# vme_can_fpga_pwr.net
KiCad netlist of a schematic drawn in Altium Designer
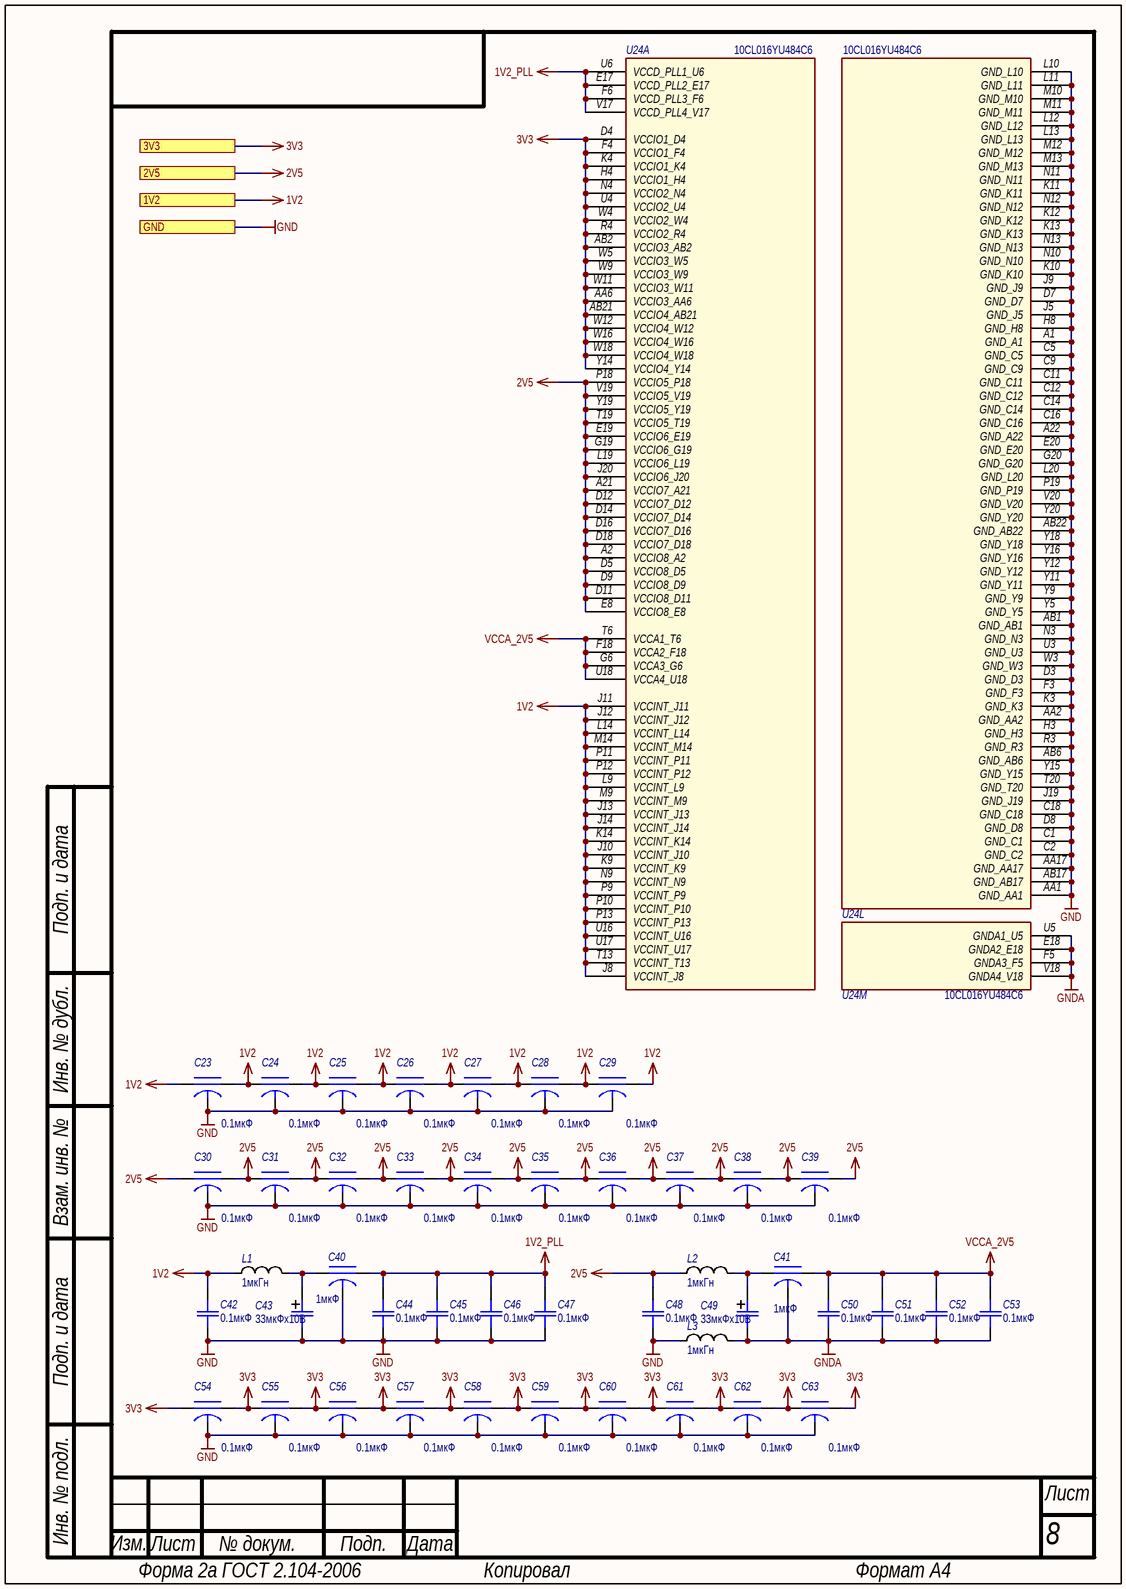
[diagram p0: vme_can_fpga_pwr.SchDoc]

(export (version "E")
  (design (tool "Eeschema 10.0.6"))
  (components
    (comp (ref "C23")
      (value "0.1мкФ")
      (footprint "3pol_SMD0402")
      (fields (field (name "Comment") "NFM15PC104D0J3"))
      (libsource (lib "Capacitop_3Pol") (part "Capacitop_3Pol"))
    )
    (comp (ref "C24")
      (value "0.1мкФ")
      (footprint "3pol_SMD0402")
      (fields (field (name "Comment") "NFM15PC104D0J3"))
      (libsource (lib "Capacitop_3Pol") (part "Capacitop_3Pol"))
    )
    (comp (ref "C25")
      (value "0.1мкФ")
      (footprint "3pol_SMD0402")
      (fields (field (name "Comment") "NFM15PC104D0J3"))
      (libsource (lib "Capacitop_3Pol") (part "Capacitop_3Pol"))
    )
    (comp (ref "C26")
      (value "0.1мкФ")
      (footprint "3pol_SMD0402")
      (fields (field (name "Comment") "NFM15PC104D0J3"))
      (libsource (lib "Capacitop_3Pol") (part "Capacitop_3Pol"))
    )
    (comp (ref "C27")
      (value "0.1мкФ")
      (footprint "3pol_SMD0402")
      (fields (field (name "Comment") "NFM15PC104D0J3"))
      (libsource (lib "Capacitop_3Pol") (part "Capacitop_3Pol"))
    )
    (comp (ref "C28")
      (value "0.1мкФ")
      (footprint "3pol_SMD0402")
      (fields (field (name "Comment") "NFM15PC104D0J3"))
      (libsource (lib "Capacitop_3Pol") (part "Capacitop_3Pol"))
    )
    (comp (ref "C29")
      (value "0.1мкФ")
      (footprint "3pol_SMD0402")
      (fields (field (name "Comment") "NFM15PC104D0J3"))
      (libsource (lib "Capacitop_3Pol") (part "Capacitop_3Pol"))
    )
    (comp (ref "C30")
      (value "0.1мкФ")
      (footprint "3pol_SMD0402")
      (fields (field (name "Comment") "NFM15PC104D0J3"))
      (libsource (lib "Capacitop_3Pol") (part "Capacitop_3Pol"))
    )
    (comp (ref "C31")
      (value "0.1мкФ")
      (footprint "3pol_SMD0402")
      (fields (field (name "Comment") "NFM15PC104D0J3"))
      (libsource (lib "Capacitop_3Pol") (part "Capacitop_3Pol"))
    )
    (comp (ref "C32")
      (value "0.1мкФ")
      (footprint "3pol_SMD0402")
      (fields (field (name "Comment") "NFM15PC104D0J3"))
      (libsource (lib "Capacitop_3Pol") (part "Capacitop_3Pol"))
    )
    (comp (ref "C33")
      (value "0.1мкФ")
      (footprint "3pol_SMD0402")
      (fields (field (name "Comment") "NFM15PC104D0J3"))
      (libsource (lib "Capacitop_3Pol") (part "Capacitop_3Pol"))
    )
    (comp (ref "C34")
      (value "0.1мкФ")
      (footprint "3pol_SMD0402")
      (fields (field (name "Comment") "NFM15PC104D0J3"))
      (libsource (lib "Capacitop_3Pol") (part "Capacitop_3Pol"))
    )
    (comp (ref "C35")
      (value "0.1мкФ")
      (footprint "3pol_SMD0402")
      (fields (field (name "Comment") "NFM15PC104D0J3"))
      (libsource (lib "Capacitop_3Pol") (part "Capacitop_3Pol"))
    )
    (comp (ref "C36")
      (value "0.1мкФ")
      (footprint "3pol_SMD0402")
      (fields (field (name "Comment") "NFM15PC104D0J3"))
      (libsource (lib "Capacitop_3Pol") (part "Capacitop_3Pol"))
    )
    (comp (ref "C37")
      (value "0.1мкФ")
      (footprint "3pol_SMD0402")
      (fields (field (name "Comment") "NFM15PC104D0J3"))
      (libsource (lib "Capacitop_3Pol") (part "Capacitop_3Pol"))
    )
    (comp (ref "C38")
      (value "0.1мкФ")
      (footprint "3pol_SMD0402")
      (fields (field (name "Comment") "NFM15PC104D0J3"))
      (libsource (lib "Capacitop_3Pol") (part "Capacitop_3Pol"))
    )
    (comp (ref "C39")
      (value "0.1мкФ")
      (footprint "3pol_SMD0402")
      (fields (field (name "Comment") "NFM15PC104D0J3"))
      (libsource (lib "Capacitop_3Pol") (part "Capacitop_3Pol"))
    )
    (comp (ref "C40")
      (value "1мкФ")
      (footprint "3pol_SMD0402")
      (fields (field (name "Comment") "NFM15PC105D0J3"))
      (libsource (lib "Capacitop_3Pol") (part "Capacitop_3Pol"))
    )
    (comp (ref "C41")
      (value "1мкФ")
      (footprint "3pol_SMD0402")
      (fields (field (name "Comment") "NFM15PC105D0J3"))
      (libsource (lib "Capacitop_3Pol") (part "Capacitop_3Pol"))
    )
    (comp (ref "C42")
      (value "0.1мкФ")
      (footprint "SMD_C0402")
      (description "Capacitor")
      (libsource (lib "Passive") (part "Capacitor"))
    )
    (comp (ref "C43")
      (value "33мкФх10В")
      (footprint "SMD_size_B")
      (description "Polarized capacitor")
      (libsource (lib "Passive") (part "Capacitor_pol"))
    )
    (comp (ref "C44")
      (value "0.1мкФ")
      (footprint "SMD_C0402")
      (description "Capacitor")
      (libsource (lib "Passive") (part "Capacitor"))
    )
    (comp (ref "C45")
      (value "0.1мкФ")
      (footprint "SMD_C0402")
      (description "Capacitor")
      (libsource (lib "Passive") (part "Capacitor"))
    )
    (comp (ref "C46")
      (value "0.1мкФ")
      (footprint "SMD_C0402")
      (description "Capacitor")
      (libsource (lib "Passive") (part "Capacitor"))
    )
    (comp (ref "C47")
      (value "0.1мкФ")
      (footprint "SMD_C0402")
      (description "Capacitor")
      (libsource (lib "Passive") (part "Capacitor"))
    )
    (comp (ref "C48")
      (value "0.1мкФ")
      (footprint "SMD_C0402")
      (description "Capacitor")
      (libsource (lib "Passive") (part "Capacitor"))
    )
    (comp (ref "C49")
      (value "33мкФх10В")
      (footprint "SMD_size_B")
      (description "Polarized capacitor")
      (libsource (lib "Passive") (part "Capacitor_pol"))
    )
    (comp (ref "C50")
      (value "0.1мкФ")
      (footprint "SMD_C0402")
      (description "Capacitor")
      (libsource (lib "Passive") (part "Capacitor"))
    )
    (comp (ref "C51")
      (value "0.1мкФ")
      (footprint "SMD_C0402")
      (description "Capacitor")
      (libsource (lib "Passive") (part "Capacitor"))
    )
    (comp (ref "C52")
      (value "0.1мкФ")
      (footprint "SMD_C0402")
      (description "Capacitor")
      (libsource (lib "Passive") (part "Capacitor"))
    )
    (comp (ref "C53")
      (value "0.1мкФ")
      (footprint "SMD_C0402")
      (description "Capacitor")
      (libsource (lib "Passive") (part "Capacitor"))
    )
    (comp (ref "C54")
      (value "0.1мкФ")
      (footprint "3pol_SMD0402")
      (fields (field (name "Comment") "NFM15PC104D0J3"))
      (libsource (lib "Capacitop_3Pol") (part "Capacitop_3Pol"))
    )
    (comp (ref "C55")
      (value "0.1мкФ")
      (footprint "3pol_SMD0402")
      (fields (field (name "Comment") "NFM15PC104D0J3"))
      (libsource (lib "Capacitop_3Pol") (part "Capacitop_3Pol"))
    )
    (comp (ref "C56")
      (value "0.1мкФ")
      (footprint "3pol_SMD0402")
      (fields (field (name "Comment") "NFM15PC104D0J3"))
      (libsource (lib "Capacitop_3Pol") (part "Capacitop_3Pol"))
    )
    (comp (ref "C57")
      (value "0.1мкФ")
      (footprint "3pol_SMD0402")
      (fields (field (name "Comment") "NFM15PC104D0J3"))
      (libsource (lib "Capacitop_3Pol") (part "Capacitop_3Pol"))
    )
    (comp (ref "C58")
      (value "0.1мкФ")
      (footprint "3pol_SMD0402")
      (fields (field (name "Comment") "NFM15PC104D0J3"))
      (libsource (lib "Capacitop_3Pol") (part "Capacitop_3Pol"))
    )
    (comp (ref "C59")
      (value "0.1мкФ")
      (footprint "3pol_SMD0402")
      (fields (field (name "Comment") "NFM15PC104D0J3"))
      (libsource (lib "Capacitop_3Pol") (part "Capacitop_3Pol"))
    )
    (comp (ref "C60")
      (value "0.1мкФ")
      (footprint "3pol_SMD0402")
      (fields (field (name "Comment") "NFM15PC104D0J3"))
      (libsource (lib "Capacitop_3Pol") (part "Capacitop_3Pol"))
    )
    (comp (ref "C61")
      (value "0.1мкФ")
      (footprint "3pol_SMD0402")
      (fields (field (name "Comment") "NFM15PC104D0J3"))
      (libsource (lib "Capacitop_3Pol") (part "Capacitop_3Pol"))
    )
    (comp (ref "C62")
      (value "0.1мкФ")
      (footprint "3pol_SMD0402")
      (fields (field (name "Comment") "NFM15PC104D0J3"))
      (libsource (lib "Capacitop_3Pol") (part "Capacitop_3Pol"))
    )
    (comp (ref "C63")
      (value "0.1мкФ")
      (footprint "3pol_SMD0402")
      (fields (field (name "Comment") "NFM15PC104D0J3"))
      (libsource (lib "Capacitop_3Pol") (part "Capacitop_3Pol"))
    )
    (comp (ref "L1")
      (value "1мкГн")
      (footprint "SMD_0805")
      (description "Inductor")
      (libsource (lib "Passive") (part "Inductor"))
    )
    (comp (ref "L2")
      (value "1мкГн")
      (footprint "SMD_0805")
      (description "Inductor")
      (libsource (lib "Passive") (part "Inductor"))
    )
    (comp (ref "L3")
      (value "1мкГн")
      (footprint "SMD_0805")
      (description "Inductor")
      (libsource (lib "Passive") (part "Inductor"))
    )
    (comp (ref "U24")
      (value "10CL016YU484")
      (footprint "UBGA-484")
      (description "Intel® Cyclone® 10 LP FPGA")
      (fields (field (name "НАИМЕНОВАНИЕ") "10CL016YU484С6"))
      (libsource (lib "FPGA") (part "10CL016_U484"))
    )
  )
  (nets
    (net (code "1") (name "1V2") (class "Default")
      (node (ref "C23") (pin "1") (pinfunction "Input_1") (pintype "passive"))
      (node (ref "C23") (pin "3") (pinfunction "Output_3") (pintype "passive"))
      (node (ref "C24") (pin "1") (pinfunction "Input_1") (pintype "passive"))
      (node (ref "C24") (pin "3") (pinfunction "Output_3") (pintype "passive"))
      (node (ref "C25") (pin "1") (pinfunction "Input_1") (pintype "passive"))
      (node (ref "C25") (pin "3") (pinfunction "Output_3") (pintype "passive"))
      (node (ref "C26") (pin "1") (pinfunction "Input_1") (pintype "passive"))
      (node (ref "C26") (pin "3") (pinfunction "Output_3") (pintype "passive"))
      (node (ref "C27") (pin "1") (pinfunction "Input_1") (pintype "passive"))
      (node (ref "C27") (pin "3") (pinfunction "Output_3") (pintype "passive"))
      (node (ref "C28") (pin "1") (pinfunction "Input_1") (pintype "passive"))
      (node (ref "C28") (pin "3") (pinfunction "Output_3") (pintype "passive"))
      (node (ref "C29") (pin "1") (pinfunction "Input_1") (pintype "passive"))
      (node (ref "C29") (pin "3") (pinfunction "Output_3") (pintype "passive"))
      (node (ref "C42") (pin "2") (pinfunction "2_2") (pintype "passive"))
      (node (ref "L1") (pin "2") (pinfunction "2_2") (pintype "passive"))
      (node (ref "U24") (pin "J10") (pinfunction "VCCINT_J10_J10") (pintype "power_in"))
      (node (ref "U24") (pin "J11") (pinfunction "VCCINT_J11_J11") (pintype "power_in"))
      (node (ref "U24") (pin "J12") (pinfunction "VCCINT_J12_J12") (pintype "power_in"))
      (node (ref "U24") (pin "J13") (pinfunction "VCCINT_J13_J13") (pintype "power_in"))
      (node (ref "U24") (pin "J14") (pinfunction "VCCINT_J14_J14") (pintype "power_in"))
      (node (ref "U24") (pin "J8") (pinfunction "VCCINT_J8_J8") (pintype "power_in"))
      (node (ref "U24") (pin "K14") (pinfunction "VCCINT_K14_K14") (pintype "power_in"))
      (node (ref "U24") (pin "K9") (pinfunction "VCCINT_K9_K9") (pintype "power_in"))
      (node (ref "U24") (pin "L14") (pinfunction "VCCINT_L14_L14") (pintype "power_in"))
      (node (ref "U24") (pin "L9") (pinfunction "VCCINT_L9_L9") (pintype "power_in"))
      (node (ref "U24") (pin "M14") (pinfunction "VCCINT_M14_M14") (pintype "power_in"))
      (node (ref "U24") (pin "M9") (pinfunction "VCCINT_M9_M9") (pintype "power_in"))
      (node (ref "U24") (pin "N9") (pinfunction "VCCINT_N9_N9") (pintype "power_in"))
      (node (ref "U24") (pin "P10") (pinfunction "VCCINT_P10_P10") (pintype "power_in"))
      (node (ref "U24") (pin "P11") (pinfunction "VCCINT_P11_P11") (pintype "power_in"))
      (node (ref "U24") (pin "P12") (pinfunction "VCCINT_P12_P12") (pintype "power_in"))
      (node (ref "U24") (pin "P13") (pinfunction "VCCINT_P13_P13") (pintype "power_in"))
      (node (ref "U24") (pin "P9") (pinfunction "VCCINT_P9_P9") (pintype "power_in"))
      (node (ref "U24") (pin "T13") (pinfunction "VCCINT_T13_T13") (pintype "power_in"))
      (node (ref "U24") (pin "U16") (pinfunction "VCCINT_U16_U16") (pintype "power_in"))
      (node (ref "U24") (pin "U17") (pinfunction "VCCINT_U17_U17") (pintype "power_in"))
    )
    (net (code "2") (name "1V2_PLL") (class "Default")
      (node (ref "C40") (pin "1") (pinfunction "Input_1") (pintype "passive"))
      (node (ref "C44") (pin "2") (pinfunction "2_2") (pintype "passive"))
      (node (ref "C45") (pin "2") (pinfunction "2_2") (pintype "passive"))
      (node (ref "C46") (pin "2") (pinfunction "2_2") (pintype "passive"))
      (node (ref "C47") (pin "2") (pinfunction "2_2") (pintype "passive"))
      (node (ref "U24") (pin "E17") (pinfunction "VCCD_PLL2_E17_E17") (pintype "power_in"))
      (node (ref "U24") (pin "F6") (pinfunction "VCCD_PLL3_F6_F6") (pintype "power_in"))
      (node (ref "U24") (pin "U6") (pinfunction "VCCD_PLL1_U6_U6") (pintype "power_in"))
      (node (ref "U24") (pin "V17") (pinfunction "VCCD_PLL4_V17_V17") (pintype "power_in"))
    )
    (net (code "3") (name "2V5") (class "Default")
      (node (ref "C30") (pin "1") (pinfunction "Input_1") (pintype "passive"))
      (node (ref "C30") (pin "3") (pinfunction "Output_3") (pintype "passive"))
      (node (ref "C31") (pin "1") (pinfunction "Input_1") (pintype "passive"))
      (node (ref "C31") (pin "3") (pinfunction "Output_3") (pintype "passive"))
      (node (ref "C32") (pin "1") (pinfunction "Input_1") (pintype "passive"))
      (node (ref "C32") (pin "3") (pinfunction "Output_3") (pintype "passive"))
      (node (ref "C33") (pin "1") (pinfunction "Input_1") (pintype "passive"))
      (node (ref "C33") (pin "3") (pinfunction "Output_3") (pintype "passive"))
      (node (ref "C34") (pin "1") (pinfunction "Input_1") (pintype "passive"))
      (node (ref "C34") (pin "3") (pinfunction "Output_3") (pintype "passive"))
      (node (ref "C35") (pin "1") (pinfunction "Input_1") (pintype "passive"))
      (node (ref "C35") (pin "3") (pinfunction "Output_3") (pintype "passive"))
      (node (ref "C36") (pin "1") (pinfunction "Input_1") (pintype "passive"))
      (node (ref "C36") (pin "3") (pinfunction "Output_3") (pintype "passive"))
      (node (ref "C37") (pin "1") (pinfunction "Input_1") (pintype "passive"))
      (node (ref "C37") (pin "3") (pinfunction "Output_3") (pintype "passive"))
      (node (ref "C38") (pin "1") (pinfunction "Input_1") (pintype "passive"))
      (node (ref "C38") (pin "3") (pinfunction "Output_3") (pintype "passive"))
      (node (ref "C39") (pin "1") (pinfunction "Input_1") (pintype "passive"))
      (node (ref "C39") (pin "3") (pinfunction "Output_3") (pintype "passive"))
      (node (ref "C48") (pin "2") (pinfunction "2_2") (pintype "passive"))
      (node (ref "L2") (pin "2") (pinfunction "2_2") (pintype "passive"))
      (node (ref "U24") (pin "A2") (pinfunction "VCCIO8_A2_A2") (pintype "power_in"))
      (node (ref "U24") (pin "A21") (pinfunction "VCCIO7_A21_A21") (pintype "power_in"))
      (node (ref "U24") (pin "D11") (pinfunction "VCCIO8_D11_D11") (pintype "power_in"))
      (node (ref "U24") (pin "D12") (pinfunction "VCCIO7_D12_D12") (pintype "power_in"))
      (node (ref "U24") (pin "D14") (pinfunction "VCCIO7_D14_D14") (pintype "power_in"))
      (node (ref "U24") (pin "D16") (pinfunction "VCCIO7_D16_D16") (pintype "power_in"))
      (node (ref "U24") (pin "D18") (pinfunction "VCCIO7_D18_D18") (pintype "power_in"))
      (node (ref "U24") (pin "D5") (pinfunction "VCCIO8_D5_D5") (pintype "power_in"))
      (node (ref "U24") (pin "D9") (pinfunction "VCCIO8_D9_D9") (pintype "power_in"))
      (node (ref "U24") (pin "E19") (pinfunction "VCCIO6_E19_E19") (pintype "power_in"))
      (node (ref "U24") (pin "E8") (pinfunction "VCCIO8_E8_E8") (pintype "power_in"))
      (node (ref "U24") (pin "G19") (pinfunction "VCCIO6_G19_G19") (pintype "power_in"))
      (node (ref "U24") (pin "J20") (pinfunction "VCCIO6_J20_J20") (pintype "power_in"))
      (node (ref "U24") (pin "L19") (pinfunction "VCCIO6_L19_L19") (pintype "power_in"))
      (node (ref "U24") (pin "P18") (pinfunction "VCCIO5_P18_P18") (pintype "power_in"))
      (node (ref "U24") (pin "T19") (pinfunction "VCCIO5_T19_T19") (pintype "power_in"))
      (node (ref "U24") (pin "V19") (pinfunction "VCCIO5_V19_V19") (pintype "power_in"))
      (node (ref "U24") (pin "Y19") (pinfunction "VCCIO5_Y19_Y19") (pintype "power_in"))
    )
    (net (code "4") (name "3V3") (class "Default")
      (node (ref "C54") (pin "1") (pinfunction "Input_1") (pintype "passive"))
      (node (ref "C54") (pin "3") (pinfunction "Output_3") (pintype "passive"))
      (node (ref "C55") (pin "1") (pinfunction "Input_1") (pintype "passive"))
      (node (ref "C55") (pin "3") (pinfunction "Output_3") (pintype "passive"))
      (node (ref "C56") (pin "1") (pinfunction "Input_1") (pintype "passive"))
      (node (ref "C56") (pin "3") (pinfunction "Output_3") (pintype "passive"))
      (node (ref "C57") (pin "1") (pinfunction "Input_1") (pintype "passive"))
      (node (ref "C57") (pin "3") (pinfunction "Output_3") (pintype "passive"))
      (node (ref "C58") (pin "1") (pinfunction "Input_1") (pintype "passive"))
      (node (ref "C58") (pin "3") (pinfunction "Output_3") (pintype "passive"))
      (node (ref "C59") (pin "1") (pinfunction "Input_1") (pintype "passive"))
      (node (ref "C59") (pin "3") (pinfunction "Output_3") (pintype "passive"))
      (node (ref "C60") (pin "1") (pinfunction "Input_1") (pintype "passive"))
      (node (ref "C60") (pin "3") (pinfunction "Output_3") (pintype "passive"))
      (node (ref "C61") (pin "1") (pinfunction "Input_1") (pintype "passive"))
      (node (ref "C61") (pin "3") (pinfunction "Output_3") (pintype "passive"))
      (node (ref "C62") (pin "1") (pinfunction "Input_1") (pintype "passive"))
      (node (ref "C62") (pin "3") (pinfunction "Output_3") (pintype "passive"))
      (node (ref "C63") (pin "1") (pinfunction "Input_1") (pintype "passive"))
      (node (ref "C63") (pin "3") (pinfunction "Output_3") (pintype "passive"))
      (node (ref "U24") (pin "AA6") (pinfunction "VCCIO3_AA6_AA6") (pintype "power_in"))
      (node (ref "U24") (pin "AB2") (pinfunction "VCCIO3_AB2_AB2") (pintype "power_in"))
      (node (ref "U24") (pin "AB21") (pinfunction "VCCIO4_AB21_AB21") (pintype "power_in"))
      (node (ref "U24") (pin "D4") (pinfunction "VCCIO1_D4_D4") (pintype "power_in"))
      (node (ref "U24") (pin "F4") (pinfunction "VCCIO1_F4_F4") (pintype "power_in"))
      (node (ref "U24") (pin "H4") (pinfunction "VCCIO1_H4_H4") (pintype "power_in"))
      (node (ref "U24") (pin "K4") (pinfunction "VCCIO1_K4_K4") (pintype "power_in"))
      (node (ref "U24") (pin "N4") (pinfunction "VCCIO2_N4_N4") (pintype "power_in"))
      (node (ref "U24") (pin "R4") (pinfunction "VCCIO2_R4_R4") (pintype "power_in"))
      (node (ref "U24") (pin "U4") (pinfunction "VCCIO2_U4_U4") (pintype "power_in"))
      (node (ref "U24") (pin "W11") (pinfunction "VCCIO3_W11_W11") (pintype "power_in"))
      (node (ref "U24") (pin "W12") (pinfunction "VCCIO4_W12_W12") (pintype "power_in"))
      (node (ref "U24") (pin "W16") (pinfunction "VCCIO4_W16_W16") (pintype "power_in"))
      (node (ref "U24") (pin "W18") (pinfunction "VCCIO4_W18_W18") (pintype "power_in"))
      (node (ref "U24") (pin "W4") (pinfunction "VCCIO2_W4_W4") (pintype "power_in"))
      (node (ref "U24") (pin "W5") (pinfunction "VCCIO3_W5_W5") (pintype "power_in"))
      (node (ref "U24") (pin "W9") (pinfunction "VCCIO3_W9_W9") (pintype "power_in"))
      (node (ref "U24") (pin "Y14") (pinfunction "VCCIO4_Y14_Y14") (pintype "power_in"))
    )
    (net (code "5") (name "GND") (class "Default")
      (node (ref "C23") (pin "2") (pinfunction "GND_2") (pintype "passive"))
      (node (ref "C24") (pin "2") (pinfunction "GND_2") (pintype "passive"))
      (node (ref "C25") (pin "2") (pinfunction "GND_2") (pintype "passive"))
      (node (ref "C26") (pin "2") (pinfunction "GND_2") (pintype "passive"))
      (node (ref "C27") (pin "2") (pinfunction "GND_2") (pintype "passive"))
      (node (ref "C28") (pin "2") (pinfunction "GND_2") (pintype "passive"))
      (node (ref "C29") (pin "2") (pinfunction "GND_2") (pintype "passive"))
      (node (ref "C30") (pin "2") (pinfunction "GND_2") (pintype "passive"))
      (node (ref "C31") (pin "2") (pinfunction "GND_2") (pintype "passive"))
      (node (ref "C32") (pin "2") (pinfunction "GND_2") (pintype "passive"))
      (node (ref "C33") (pin "2") (pinfunction "GND_2") (pintype "passive"))
      (node (ref "C34") (pin "2") (pinfunction "GND_2") (pintype "passive"))
      (node (ref "C35") (pin "2") (pinfunction "GND_2") (pintype "passive"))
      (node (ref "C36") (pin "2") (pinfunction "GND_2") (pintype "passive"))
      (node (ref "C37") (pin "2") (pinfunction "GND_2") (pintype "passive"))
      (node (ref "C38") (pin "2") (pinfunction "GND_2") (pintype "passive"))
      (node (ref "C39") (pin "2") (pinfunction "GND_2") (pintype "passive"))
      (node (ref "C40") (pin "2") (pinfunction "GND_2") (pintype "passive"))
      (node (ref "C42") (pin "1") (pinfunction "1_1") (pintype "passive"))
      (node (ref "C43") (pin "2") (pinfunction "2_2") (pintype "passive"))
      (node (ref "C44") (pin "1") (pinfunction "1_1") (pintype "passive"))
      (node (ref "C45") (pin "1") (pinfunction "1_1") (pintype "passive"))
      (node (ref "C46") (pin "1") (pinfunction "1_1") (pintype "passive"))
      (node (ref "C47") (pin "1") (pinfunction "1_1") (pintype "passive"))
      (node (ref "C48") (pin "1") (pinfunction "1_1") (pintype "passive"))
      (node (ref "C54") (pin "2") (pinfunction "GND_2") (pintype "passive"))
      (node (ref "C55") (pin "2") (pinfunction "GND_2") (pintype "passive"))
      (node (ref "C56") (pin "2") (pinfunction "GND_2") (pintype "passive"))
      (node (ref "C57") (pin "2") (pinfunction "GND_2") (pintype "passive"))
      (node (ref "C58") (pin "2") (pinfunction "GND_2") (pintype "passive"))
      (node (ref "C59") (pin "2") (pinfunction "GND_2") (pintype "passive"))
      (node (ref "C60") (pin "2") (pinfunction "GND_2") (pintype "passive"))
      (node (ref "C61") (pin "2") (pinfunction "GND_2") (pintype "passive"))
      (node (ref "C62") (pin "2") (pinfunction "GND_2") (pintype "passive"))
      (node (ref "C63") (pin "2") (pinfunction "GND_2") (pintype "passive"))
      (node (ref "L3") (pin "2") (pinfunction "2_2") (pintype "passive"))
      (node (ref "U24") (pin "A1") (pinfunction "GND_A1_A1") (pintype "power_in"))
      (node (ref "U24") (pin "A22") (pinfunction "GND_A22_A22") (pintype "power_in"))
      (node (ref "U24") (pin "AA1") (pinfunction "GND_AA1_AA1") (pintype "power_in"))
      (node (ref "U24") (pin "AA17") (pinfunction "GND_AA17_AA17") (pintype "power_in"))
      (node (ref "U24") (pin "AA2") (pinfunction "GND_AA2_AA2") (pintype "power_in"))
      (node (ref "U24") (pin "AB1") (pinfunction "GND_AB1_AB1") (pintype "power_in"))
      (node (ref "U24") (pin "AB17") (pinfunction "GND_AB17_AB17") (pintype "power_in"))
      (node (ref "U24") (pin "AB22") (pinfunction "GND_AB22_AB22") (pintype "power_in"))
      (node (ref "U24") (pin "AB6") (pinfunction "GND_AB6_AB6") (pintype "power_in"))
      (node (ref "U24") (pin "C1") (pinfunction "GND_C1_C1") (pintype "power_in"))
      (node (ref "U24") (pin "C11") (pinfunction "GND_C11_C11") (pintype "power_in"))
      (node (ref "U24") (pin "C12") (pinfunction "GND_C12_C12") (pintype "power_in"))
      (node (ref "U24") (pin "C14") (pinfunction "GND_C14_C14") (pintype "power_in"))
      (node (ref "U24") (pin "C16") (pinfunction "GND_C16_C16") (pintype "power_in"))
      (node (ref "U24") (pin "C18") (pinfunction "GND_C18_C18") (pintype "power_in"))
      (node (ref "U24") (pin "C2") (pinfunction "GND_C2_C2") (pintype "power_in"))
      (node (ref "U24") (pin "C5") (pinfunction "GND_C5_C5") (pintype "power_in"))
      (node (ref "U24") (pin "C9") (pinfunction "GND_C9_C9") (pintype "power_in"))
      (node (ref "U24") (pin "D3") (pinfunction "GND_D3_D3") (pintype "power_in"))
      (node (ref "U24") (pin "D7") (pinfunction "GND_D7_D7") (pintype "power_in"))
      (node (ref "U24") (pin "D8") (pinfunction "GND_D8_D8") (pintype "power_in"))
      (node (ref "U24") (pin "E20") (pinfunction "GND_E20_E20") (pintype "power_in"))
      (node (ref "U24") (pin "F3") (pinfunction "GND_F3_F3") (pintype "power_in"))
      (node (ref "U24") (pin "G20") (pinfunction "GND_G20_G20") (pintype "power_in"))
      (node (ref "U24") (pin "H3") (pinfunction "GND_H3_H3") (pintype "power_in"))
      (node (ref "U24") (pin "H8") (pinfunction "GND_H8_H8") (pintype "power_in"))
      (node (ref "U24") (pin "J19") (pinfunction "GND_J19_J19") (pintype "power_in"))
      (node (ref "U24") (pin "J5") (pinfunction "GND_J5_J5") (pintype "power_in"))
      (node (ref "U24") (pin "J9") (pinfunction "GND_J9_J9") (pintype "power_in"))
      (node (ref "U24") (pin "K10") (pinfunction "GND_K10_K10") (pintype "power_in"))
      (node (ref "U24") (pin "K11") (pinfunction "GND_K11_K11") (pintype "power_in"))
      (node (ref "U24") (pin "K12") (pinfunction "GND_K12_K12") (pintype "power_in"))
      (node (ref "U24") (pin "K13") (pinfunction "GND_K13_K13") (pintype "power_in"))
      (node (ref "U24") (pin "K3") (pinfunction "GND_K3_K3") (pintype "power_in"))
      (node (ref "U24") (pin "L10") (pinfunction "GND_L10_L10") (pintype "power_in"))
      (node (ref "U24") (pin "L11") (pinfunction "GND_L11_L11") (pintype "power_in"))
      (node (ref "U24") (pin "L12") (pinfunction "GND_L12_L12") (pintype "power_in"))
      (node (ref "U24") (pin "L13") (pinfunction "GND_L13_L13") (pintype "power_in"))
      (node (ref "U24") (pin "L20") (pinfunction "GND_L20_L20") (pintype "power_in"))
      (node (ref "U24") (pin "M10") (pinfunction "GND_M10_M10") (pintype "power_in"))
      (node (ref "U24") (pin "M11") (pinfunction "GND_M11_M11") (pintype "power_in"))
      (node (ref "U24") (pin "M12") (pinfunction "GND_M12_M12") (pintype "power_in"))
      (node (ref "U24") (pin "M13") (pinfunction "GND_M13_M13") (pintype "power_in"))
      (node (ref "U24") (pin "N10") (pinfunction "GND_N10_N10") (pintype "power_in"))
      (node (ref "U24") (pin "N11") (pinfunction "GND_N11_N11") (pintype "power_in"))
      (node (ref "U24") (pin "N12") (pinfunction "GND_N12_N12") (pintype "power_in"))
      (node (ref "U24") (pin "N13") (pinfunction "GND_N13_N13") (pintype "power_in"))
      (node (ref "U24") (pin "N3") (pinfunction "GND_N3_N3") (pintype "power_in"))
      (node (ref "U24") (pin "P19") (pinfunction "GND_P19_P19") (pintype "power_in"))
      (node (ref "U24") (pin "R3") (pinfunction "GND_R3_R3") (pintype "power_in"))
      (node (ref "U24") (pin "T20") (pinfunction "GND_T20_T20") (pintype "power_in"))
      (node (ref "U24") (pin "U3") (pinfunction "GND_U3_U3") (pintype "power_in"))
      (node (ref "U24") (pin "V20") (pinfunction "GND_V20_V20") (pintype "power_in"))
      (node (ref "U24") (pin "W3") (pinfunction "GND_W3_W3") (pintype "power_in"))
      (node (ref "U24") (pin "Y11") (pinfunction "GND_Y11_Y11") (pintype "power_in"))
      (node (ref "U24") (pin "Y12") (pinfunction "GND_Y12_Y12") (pintype "power_in"))
      (node (ref "U24") (pin "Y15") (pinfunction "GND_Y15_Y15") (pintype "power_in"))
      (node (ref "U24") (pin "Y16") (pinfunction "GND_Y16_Y16") (pintype "power_in"))
      (node (ref "U24") (pin "Y18") (pinfunction "GND_Y18_Y18") (pintype "power_in"))
      (node (ref "U24") (pin "Y20") (pinfunction "GND_Y20_Y20") (pintype "power_in"))
      (node (ref "U24") (pin "Y5") (pinfunction "GND_Y5_Y5") (pintype "power_in"))
      (node (ref "U24") (pin "Y9") (pinfunction "GND_Y9_Y9") (pintype "power_in"))
    )
    (net (code "6") (name "GNDA") (class "Default")
      (node (ref "C41") (pin "2") (pinfunction "GND_2") (pintype "passive"))
      (node (ref "C49") (pin "2") (pinfunction "2_2") (pintype "passive"))
      (node (ref "C50") (pin "1") (pinfunction "1_1") (pintype "passive"))
      (node (ref "C51") (pin "1") (pinfunction "1_1") (pintype "passive"))
      (node (ref "C52") (pin "1") (pinfunction "1_1") (pintype "passive"))
      (node (ref "C53") (pin "1") (pinfunction "1_1") (pintype "passive"))
      (node (ref "L3") (pin "1") (pinfunction "1_1") (pintype "passive"))
      (node (ref "U24") (pin "E18") (pinfunction "GNDA2_E18_E18") (pintype "power_in"))
      (node (ref "U24") (pin "F5") (pinfunction "GNDA3_F5_F5") (pintype "power_in"))
      (node (ref "U24") (pin "U5") (pinfunction "GNDA1_U5_U5") (pintype "power_in"))
      (node (ref "U24") (pin "V18") (pinfunction "GNDA4_V18_V18") (pintype "power_in"))
    )
    (net (code "7") (name "Net-(C40-Output)") (class "Default")
      (node (ref "C40") (pin "3") (pinfunction "Output_3") (pintype "passive"))
      (node (ref "C43") (pin "1") (pinfunction "1_1") (pintype "passive"))
      (node (ref "L1") (pin "1") (pinfunction "1_1") (pintype "passive"))
    )
    (net (code "8") (name "Net-(C41-Output)") (class "Default")
      (node (ref "C41") (pin "3") (pinfunction "Output_3") (pintype "passive"))
      (node (ref "C49") (pin "1") (pinfunction "1_1") (pintype "passive"))
      (node (ref "L2") (pin "1") (pinfunction "1_1") (pintype "passive"))
    )
    (net (code "9") (name "VCCA_2V5") (class "Default")
      (node (ref "C41") (pin "1") (pinfunction "Input_1") (pintype "passive"))
      (node (ref "C50") (pin "2") (pinfunction "2_2") (pintype "passive"))
      (node (ref "C51") (pin "2") (pinfunction "2_2") (pintype "passive"))
      (node (ref "C52") (pin "2") (pinfunction "2_2") (pintype "passive"))
      (node (ref "C53") (pin "2") (pinfunction "2_2") (pintype "passive"))
      (node (ref "U24") (pin "F18") (pinfunction "VCCA2_F18_F18") (pintype "power_in"))
      (node (ref "U24") (pin "G6") (pinfunction "VCCA3_G6_G6") (pintype "power_in"))
      (node (ref "U24") (pin "T6") (pinfunction "VCCA1_T6_T6") (pintype "power_in"))
      (node (ref "U24") (pin "U18") (pinfunction "VCCA4_U18_U18") (pintype "power_in"))
    )
  )
)
